# ArduinoRadioV1.net
KiCad netlist of a schematic drawn in EAGLE
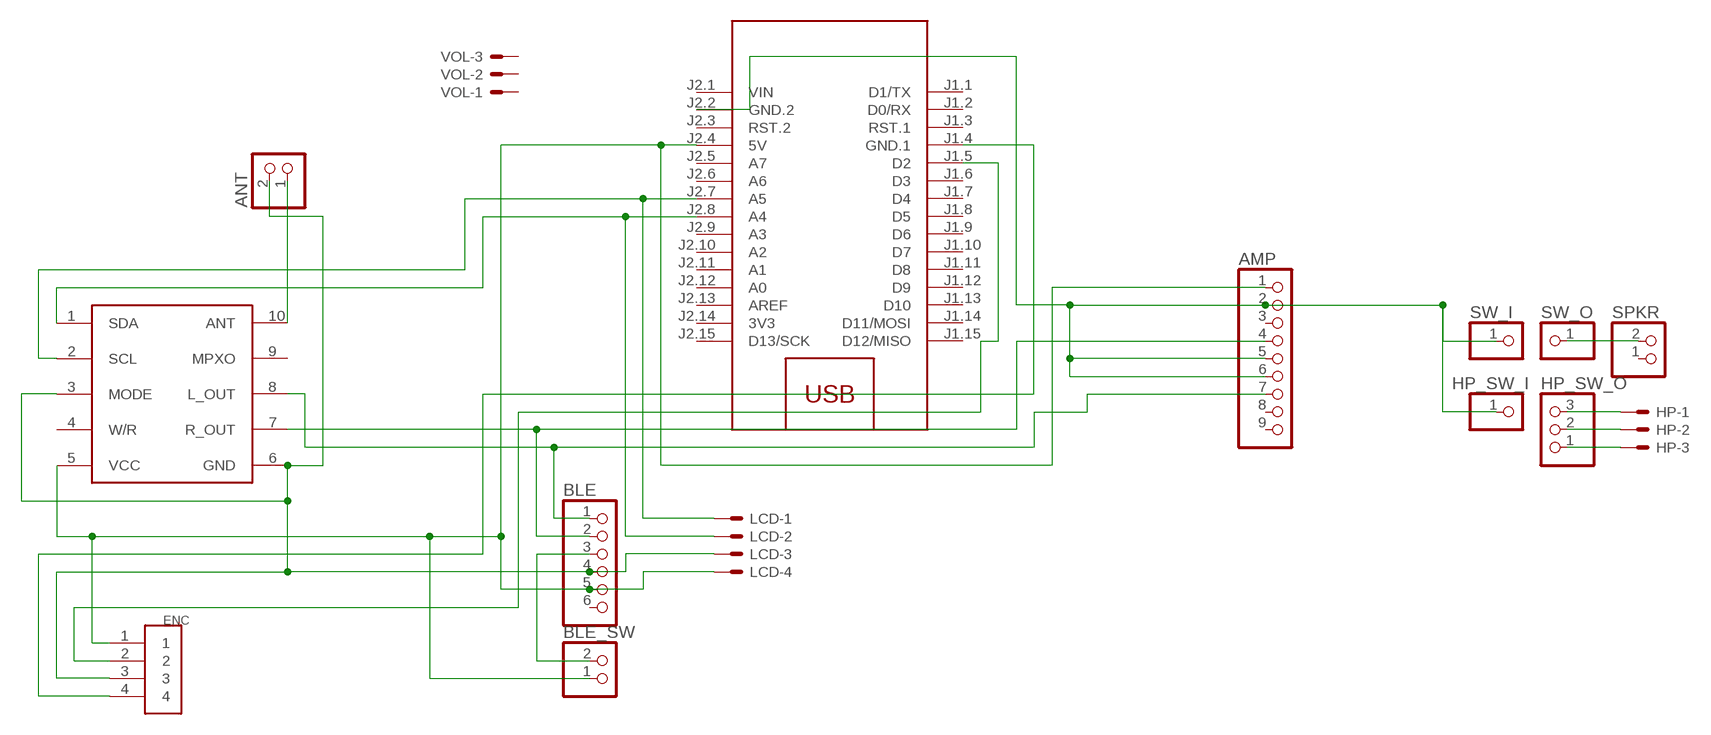
[diagram p0: schematic, sheet 1]

(export (version "E")
  (design (tool "Eeschema 10.0.6"))
  (components
    (comp (ref "AMP")
      (value "PINHD-1X9")
      (footprint "eagle-import:1X09-BIG")
      (libsource (lib "eagle-import") (part "PINHD-1X9"))
    )
    (comp (ref "ANT")
      (value "JST_2PIN-THM")
      (footprint "eagle-import:JST-PH-2-THM")
      (libsource (lib "eagle-import") (part "JST_2PIN-THM"))
    )
    (comp (ref "BLE")
      (value "PINHD-1X6")
      (footprint "eagle-import:1X06")
      (libsource (lib "eagle-import") (part "PINHD-1X6"))
    )
    (comp (ref "BLE_SW")
      (value "JST_2PIN-THM")
      (footprint "eagle-import:JST-PH-2-THM")
      (libsource (lib "eagle-import") (part "JST_2PIN-THM"))
    )
    (comp (ref "ENC")
      (value "1X4-BIG")
      (footprint "eagle-import:1X04-BIG")
      (libsource (lib "eagle-import") (part "1X4-BIG"))
    )
    (comp (ref "HP")
      (value "JST-XH-03-PIN-ROUND-PAD")
      (footprint "eagle-import:JST-XH-03-PACKAGE-ROUND-PAD")
      (libsource (lib "eagle-import") (part "JST-XH-03-PIN-ROUND-PAD"))
    )
    (comp (ref "HP_SW_I")
      (value "PINHD-1X1")
      (footprint "eagle-import:1X01")
      (libsource (lib "eagle-import") (part "PINHD-1X1"))
    )
    (comp (ref "HP_SW_O")
      (value "PINHD-1X3")
      (footprint "eagle-import:1X03")
      (libsource (lib "eagle-import") (part "PINHD-1X3"))
    )
    (comp (ref "LCD")
      (value "JST-XH-04-PIN-ROUND-PAD")
      (footprint "eagle-import:JST-XH-04-PACKAGE-ROUND-PAD")
      (libsource (lib "eagle-import") (part "JST-XH-04-PIN-ROUND-PAD"))
    )
    (comp (ref "M1")
      (value "ARDUINO-NANO-3.0")
      (footprint "eagle-import:ARDUINO-NANO-3.0")
      (libsource (lib "eagle-import") (part "ARDUINO-NANO-3.0"))
    )
    (comp (ref "SPKR")
      (value "JST_2PIN-THM")
      (footprint "eagle-import:JST-PH-2-THM")
      (libsource (lib "eagle-import") (part "JST_2PIN-THM"))
    )
    (comp (ref "SW_I")
      (value "PINHD-1X1")
      (footprint "eagle-import:1X01")
      (libsource (lib "eagle-import") (part "PINHD-1X1"))
    )
    (comp (ref "SW_O")
      (value "PINHD-1X1")
      (footprint "eagle-import:1X01")
      (libsource (lib "eagle-import") (part "PINHD-1X1"))
    )
    (comp (ref "TEA5767")
      (value "TEA5767BREAKOUT")
      (footprint "eagle-import:TEA5767MM2")
      (libsource (lib "eagle-import") (part "TEA5767BREAKOUT"))
    )
    (comp (ref "VOL")
      (value "JST-XH-03-PIN-ROUND-PAD")
      (footprint "eagle-import:JST-XH-03-PACKAGE-ROUND-PAD")
      (libsource (lib "eagle-import") (part "JST-XH-03-PIN-ROUND-PAD"))
    )
  )
  (nets
    (net (code "1") (name "/3V3") (class "Default")
      (node (ref "M1") (pin "J2.14") (pinfunction "3V3_J2.14") (pintype "power_in"))
    )
    (net (code "2") (name "/R_OUT") (class "Default")
      (node (ref "AMP") (pin "2") (pinfunction "2_2") (pintype "passive"))
      (node (ref "AMP") (pin "4") (pinfunction "4_4") (pintype "passive"))
      (node (ref "AMP") (pin "5") (pinfunction "5_5") (pintype "passive"))
      (node (ref "AMP") (pin "6") (pinfunction "6_6") (pintype "passive"))
      (node (ref "BLE") (pin "2") (pinfunction "2_2") (pintype "passive"))
      (node (ref "HP_SW_I") (pin "1") (pinfunction "1_1") (pintype "passive"))
      (node (ref "M1") (pin "J2.2") (pinfunction "GND.2_J2.2") (pintype "power_in"))
      (node (ref "SW_I") (pin "1") (pinfunction "1_1") (pintype "passive"))
      (node (ref "TEA5767") (pin "7") (pinfunction "R_OUT_7") (pintype "bidirectional"))
    )
    (net (code "3") (name "/VIN") (class "Default")
      (node (ref "M1") (pin "J2.1") (pinfunction "VIN_J2.1") (pintype "power_in"))
    )
    (net (code "4") (name "Net-(ANT-1)") (class "Default")
      (node (ref "ANT") (pin "2") (pinfunction "1_2") (pintype "passive"))
      (node (ref "BLE") (pin "4") (pinfunction "4_4") (pintype "passive"))
      (node (ref "ENC") (pin "3") (pinfunction "3_3") (pintype "bidirectional"))
      (node (ref "LCD") (pin "3") (pinfunction "S_3") (pintype "passive"))
      (node (ref "TEA5767") (pin "3") (pinfunction "MODE_3") (pintype "bidirectional"))
      (node (ref "TEA5767") (pin "6") (pinfunction "GND_6") (pintype "bidirectional"))
    )
    (net (code "5") (name "Net-(ANT-2)") (class "Default")
      (node (ref "ANT") (pin "1") (pinfunction "2_1") (pintype "passive"))
      (node (ref "TEA5767") (pin "10") (pinfunction "ANT_10") (pintype "bidirectional"))
    )
    (net (code "6") (name "Net-(BLE_SW-1)") (class "Default")
      (node (ref "BLE") (pin "3") (pinfunction "3_3") (pintype "passive"))
      (node (ref "BLE_SW") (pin "2") (pinfunction "1_2") (pintype "passive"))
    )
    (net (code "7") (name "Net-(BLE_SW-2)") (class "Default")
      (node (ref "AMP") (pin "1") (pinfunction "1_1") (pintype "passive"))
      (node (ref "BLE") (pin "5") (pinfunction "5_5") (pintype "passive"))
      (node (ref "BLE_SW") (pin "1") (pinfunction "2_1") (pintype "passive"))
      (node (ref "ENC") (pin "1") (pinfunction "1_1") (pintype "bidirectional"))
      (node (ref "LCD") (pin "4") (pinfunction "S_4") (pintype "passive"))
      (node (ref "M1") (pin "J2.4") (pinfunction "5V_J2.4") (pintype "power_in"))
      (node (ref "TEA5767") (pin "5") (pinfunction "VCC_5") (pintype "bidirectional"))
    )
    (net (code "8") (name "Net-(HPA-S)") (class "Default")
      (node (ref "HP") (pin "1") (pinfunction "S_1") (pintype "passive"))
      (node (ref "HP_SW_O") (pin "3") (pinfunction "3_3") (pintype "passive"))
    )
    (net (code "9") (name "Net-(HPB-S)") (class "Default")
      (node (ref "HP") (pin "2") (pinfunction "S_2") (pintype "passive"))
      (node (ref "HP_SW_O") (pin "2") (pinfunction "2_2") (pintype "passive"))
    )
    (net (code "10") (name "Net-(HPC-S)") (class "Default")
      (node (ref "HP") (pin "3") (pinfunction "S_3") (pintype "passive"))
      (node (ref "HP_SW_O") (pin "1") (pinfunction "1_1") (pintype "passive"))
    )
    (net (code "11") (name "Net-(LCDA-S)") (class "Default")
      (node (ref "LCD") (pin "1") (pinfunction "S_1") (pintype "passive"))
      (node (ref "M1") (pin "J2.7") (pinfunction "A5_J2.7") (pintype "bidirectional"))
      (node (ref "TEA5767") (pin "2") (pinfunction "SCL_2") (pintype "bidirectional"))
    )
    (net (code "12") (name "Net-(LCDB-S)") (class "Default")
      (node (ref "LCD") (pin "2") (pinfunction "S_2") (pintype "passive"))
      (node (ref "M1") (pin "J2.8") (pinfunction "A4_J2.8") (pintype "bidirectional"))
      (node (ref "TEA5767") (pin "1") (pinfunction "SDA_1") (pintype "bidirectional"))
    )
    (net (code "13") (name "Net-(M1-D2)") (class "Default")
      (node (ref "ENC") (pin "2") (pinfunction "2_2") (pintype "bidirectional"))
      (node (ref "M1") (pin "J1.5") (pinfunction "D2_J1.5") (pintype "bidirectional"))
    )
    (net (code "14") (name "Net-(M1-GND.1)") (class "Default")
      (node (ref "ENC") (pin "4") (pinfunction "4_4") (pintype "bidirectional"))
      (node (ref "M1") (pin "J1.4") (pinfunction "GND.1_J1.4") (pintype "power_in"))
    )
    (net (code "15") (name "Net-(SPKR-1)") (class "Default")
      (node (ref "SPKR") (pin "2") (pinfunction "1_2") (pintype "passive"))
      (node (ref "SW_O") (pin "1") (pinfunction "1_1") (pintype "passive"))
    )
    (net (code "16") (name "Net-(TEA5767-L_OUT)") (class "Default")
      (node (ref "AMP") (pin "7") (pinfunction "7_7") (pintype "passive"))
      (node (ref "BLE") (pin "1") (pinfunction "1_1") (pintype "passive"))
      (node (ref "TEA5767") (pin "8") (pinfunction "L_OUT_8") (pintype "bidirectional"))
    )
    (net (code "17") (name "unconnected-(AMP-Pad3)") (class "Default")
      (node (ref "AMP") (pin "3") (pinfunction "3_3") (pintype "passive"))
    )
    (net (code "18") (name "unconnected-(AMP-Pad8)") (class "Default")
      (node (ref "AMP") (pin "8") (pinfunction "8_8") (pintype "passive"))
    )
    (net (code "19") (name "unconnected-(AMP-Pad9)") (class "Default")
      (node (ref "AMP") (pin "9") (pinfunction "9_9") (pintype "passive"))
    )
    (net (code "20") (name "unconnected-(BLE-Pad6)") (class "Default")
      (node (ref "BLE") (pin "6") (pinfunction "6_6") (pintype "passive"))
    )
    (net (code "21") (name "unconnected-(M1-A0-PadJ2.12)") (class "Default")
      (node (ref "M1") (pin "J2.12") (pinfunction "A0_J2.12") (pintype "bidirectional"))
    )
    (net (code "22") (name "unconnected-(M1-A1-PadJ2.11)") (class "Default")
      (node (ref "M1") (pin "J2.11") (pinfunction "A1_J2.11") (pintype "bidirectional"))
    )
    (net (code "23") (name "unconnected-(M1-A2-PadJ2.10)") (class "Default")
      (node (ref "M1") (pin "J2.10") (pinfunction "A2_J2.10") (pintype "bidirectional"))
    )
    (net (code "24") (name "unconnected-(M1-A3-PadJ2.9)") (class "Default")
      (node (ref "M1") (pin "J2.9") (pinfunction "A3_J2.9") (pintype "bidirectional"))
    )
    (net (code "25") (name "unconnected-(M1-A6-PadJ2.6)") (class "Default")
      (node (ref "M1") (pin "J2.6") (pinfunction "A6_J2.6") (pintype "bidirectional"))
    )
    (net (code "26") (name "unconnected-(M1-A7-PadJ2.5)") (class "Default")
      (node (ref "M1") (pin "J2.5") (pinfunction "A7_J2.5") (pintype "bidirectional"))
    )
    (net (code "27") (name "unconnected-(M1-AREF-PadJ2.13)") (class "Default")
      (node (ref "M1") (pin "J2.13") (pinfunction "AREF_J2.13") (pintype "bidirectional"))
    )
    (net (code "28") (name "unconnected-(M1-D0{slash}RX-PadJ1.2)") (class "Default")
      (node (ref "M1") (pin "J1.2") (pinfunction "D0/RX_J1.2") (pintype "bidirectional"))
    )
    (net (code "29") (name "unconnected-(M1-D1{slash}TX-PadJ1.1)") (class "Default")
      (node (ref "M1") (pin "J1.1") (pinfunction "D1/TX_J1.1") (pintype "bidirectional"))
    )
    (net (code "30") (name "unconnected-(M1-D3-PadJ1.6)") (class "Default")
      (node (ref "M1") (pin "J1.6") (pinfunction "D3_J1.6") (pintype "bidirectional"))
    )
    (net (code "31") (name "unconnected-(M1-D4-PadJ1.7)") (class "Default")
      (node (ref "M1") (pin "J1.7") (pinfunction "D4_J1.7") (pintype "bidirectional"))
    )
    (net (code "32") (name "unconnected-(M1-D5-PadJ1.8)") (class "Default")
      (node (ref "M1") (pin "J1.8") (pinfunction "D5_J1.8") (pintype "bidirectional"))
    )
    (net (code "33") (name "unconnected-(M1-D6-PadJ1.9)") (class "Default")
      (node (ref "M1") (pin "J1.9") (pinfunction "D6_J1.9") (pintype "bidirectional"))
    )
    (net (code "34") (name "unconnected-(M1-D7-PadJ1.10)") (class "Default")
      (node (ref "M1") (pin "J1.10") (pinfunction "D7_J1.10") (pintype "bidirectional"))
    )
    (net (code "35") (name "unconnected-(M1-D8-PadJ1.11)") (class "Default")
      (node (ref "M1") (pin "J1.11") (pinfunction "D8_J1.11") (pintype "bidirectional"))
    )
    (net (code "36") (name "unconnected-(M1-D9-PadJ1.12)") (class "Default")
      (node (ref "M1") (pin "J1.12") (pinfunction "D9_J1.12") (pintype "bidirectional"))
    )
    (net (code "37") (name "unconnected-(M1-D10-PadJ1.13)") (class "Default")
      (node (ref "M1") (pin "J1.13") (pinfunction "D10_J1.13") (pintype "bidirectional"))
    )
    (net (code "38") (name "unconnected-(M1-D11{slash}MOSI-PadJ1.14)") (class "Default")
      (node (ref "M1") (pin "J1.14") (pinfunction "D11/MOSI_J1.14") (pintype "bidirectional"))
    )
    (net (code "39") (name "unconnected-(M1-D12{slash}MISO-PadJ1.15)") (class "Default")
      (node (ref "M1") (pin "J1.15") (pinfunction "D12/MISO_J1.15") (pintype "bidirectional"))
    )
    (net (code "40") (name "unconnected-(M1-D13{slash}SCK-PadJ2.15)") (class "Default")
      (node (ref "M1") (pin "J2.15") (pinfunction "D13/SCK_J2.15") (pintype "bidirectional"))
    )
    (net (code "41") (name "unconnected-(M1-RST.1-PadJ1.3)") (class "Default")
      (node (ref "M1") (pin "J1.3") (pinfunction "RST.1_J1.3") (pintype "bidirectional"))
    )
    (net (code "42") (name "unconnected-(M1-RST.2-PadJ2.3)") (class "Default")
      (node (ref "M1") (pin "J2.3") (pinfunction "RST.2_J2.3") (pintype "bidirectional"))
    )
    (net (code "43") (name "unconnected-(SPKR-2-Pad1)") (class "Default")
      (node (ref "SPKR") (pin "1") (pinfunction "2_1") (pintype "passive"))
    )
    (net (code "44") (name "unconnected-(TEA5767-MPXO-Pad9)") (class "Default")
      (node (ref "TEA5767") (pin "9") (pinfunction "MPXO_9") (pintype "bidirectional"))
    )
    (net (code "45") (name "unconnected-(TEA5767-W{slash}R-Pad4)") (class "Default")
      (node (ref "TEA5767") (pin "4") (pinfunction "W/R_4") (pintype "bidirectional"))
    )
    (net (code "46") (name "unconnected-(VOLA-S-Pad1)") (class "Default")
      (node (ref "VOL") (pin "1") (pinfunction "S_1") (pintype "passive"))
    )
    (net (code "47") (name "unconnected-(VOLB-S-Pad2)") (class "Default")
      (node (ref "VOL") (pin "2") (pinfunction "S_2") (pintype "passive"))
    )
    (net (code "48") (name "unconnected-(VOLC-S-Pad3)") (class "Default")
      (node (ref "VOL") (pin "3") (pinfunction "S_3") (pintype "passive"))
    )
  )
)
